# Power.net
KiCad netlist of a schematic drawn in Altium Designer
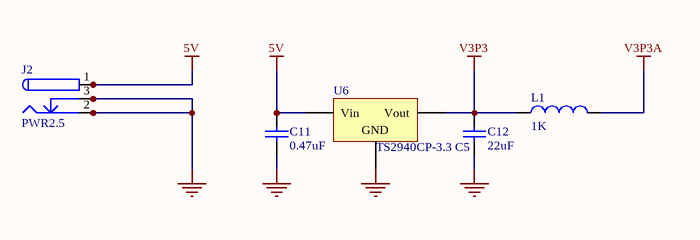
[diagram p0: Power.SchDoc]

(export (version "E")
  (design (tool "Eeschema 10.0.6"))
  (components
    (comp (ref "C11")
      (value "0.47uF")
      (footprint "0603")
      (description "Capacitor")
      (fields (field (name "PUBLISHER") "Altium Limited"))
      (libsource (lib "Miscellaneous Devices") (part "Cap"))
    )
    (comp (ref "C12")
      (value "22uF")
      (footprint "0603")
      (description "Capacitor")
      (fields (field (name "PUBLISHER") "Altium Limited"))
      (libsource (lib "Miscellaneous Devices") (part "Cap"))
    )
    (comp (ref "J2")
      (value "PWR2.5")
      (footprint "MJ-179PH")
      (description "Low Voltage Power Supply Connector")
      (libsource (lib "Miscellaneous Connectors") (part "PWR2.5"))
    )
    (comp (ref "L1")
      (value "1K")
      (footprint "0603")
      (description "Inductor")
      (fields (field (name "PUBLISHER") "Altium Limited"))
      (libsource (lib "Miscellaneous Devices") (part "Inductor"))
    )
    (comp (ref "U6")
      (value "TS2940CP-3.3 C5")
      (footprint "TS2940CP-3.3 C5")
      (description "Voltage Regulator")
      (libsource (lib "Miscellaneous Devices") (part "Volt Reg"))
    )
  )
  (nets
    (net (code "1") (name "5V") (class "Default")
      (node (ref "C11") (pin "2") (pinfunction "2_2") (pintype "passive"))
      (node (ref "J2") (pin "1") (pinfunction "1_1") (pintype "power_in"))
      (node (ref "J2") (pin "1A") (pinfunction "1A_1A") (pintype "power_in"))
      (node (ref "J2") (pin "1B") (pinfunction "1B_1B") (pintype "power_in"))
      (node (ref "U6") (pin "1") (pinfunction "Vin_1") (pintype "passive"))
    )
    (net (code "2") (name "GND") (class "Default")
      (node (ref "C11") (pin "1") (pinfunction "1_1") (pintype "passive"))
      (node (ref "C12") (pin "1") (pinfunction "1_1") (pintype "passive"))
      (node (ref "J2") (pin "2") (pinfunction "2_2") (pintype "power_in"))
      (node (ref "J2") (pin "2A") (pinfunction "2A_2A") (pintype "power_in"))
      (node (ref "J2") (pin "2B") (pinfunction "2B_2B") (pintype "power_in"))
      (node (ref "J2") (pin "3") (pinfunction "3_3") (pintype "power_in"))
      (node (ref "J2") (pin "3A") (pinfunction "3A_3A") (pintype "power_in"))
      (node (ref "J2") (pin "3B") (pinfunction "3B_3B") (pintype "power_in"))
      (node (ref "U6") (pin "2") (pinfunction "GND_2") (pintype "passive"))
    )
    (net (code "3") (name "V3P3") (class "Default")
      (node (ref "C12") (pin "2") (pinfunction "2_2") (pintype "passive"))
      (node (ref "L1") (pin "1") (pinfunction "1_1") (pintype "passive"))
      (node (ref "U6") (pin "3") (pinfunction "Vout_3") (pintype "passive"))
    )
    (net (code "4") (name "V3P3A") (class "Default")
      (node (ref "L1") (pin "2") (pinfunction "2_2") (pintype "passive"))
    )
  )
)
